# mechanical_marking.net
KiCad netlist of a schematic drawn in Altium Designer
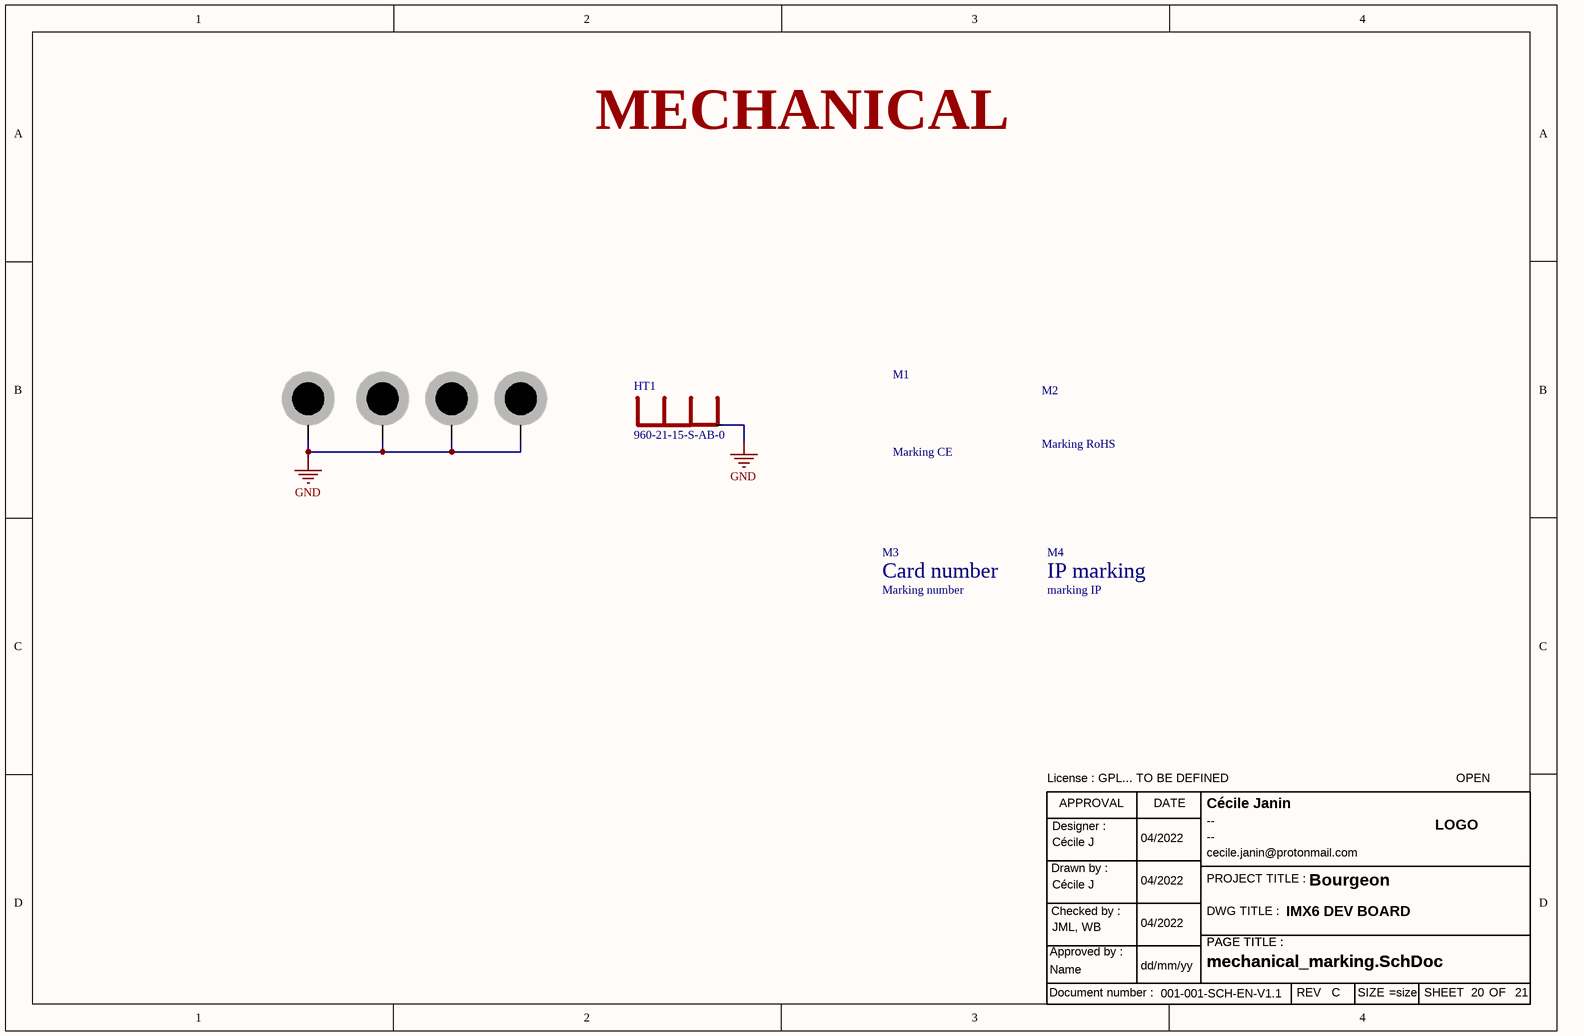
[diagram p0: mechanical_marking.SchDoc]

(export (version "E")
  (design (tool "Eeschema 10.0.6"))
  (components
    (comp (ref "HT1")
      (value "960-21-15-S-AB-0")
      (footprint "Heatsink BGA 21x21mm")
      (description "Heatsink : 960-21-15-S-AB-0\r\n6°/W @ 200LFM")
      (libsource (lib "First Board IMX6") (part "Heatsink BGA 21x21mm"))
    )
    (comp (ref "M1")
      (value "Marking CE")
      (footprint "MARKING CE")
      (description "CE marking")
      (libsource (lib "First Board IMX6") (part "Marking CE"))
    )
    (comp (ref "M2")
      (value "Marking RoHS")
      (footprint "MARKING ROHS")
      (description "RoHS marking")
      (libsource (lib "First Board IMX6") (part "Marking RoHS"))
    )
    (comp (ref "M3")
      (value "Marking number")
      (footprint "MARKING number")
      (description "Card number")
      (libsource (lib "First Board IMX6") (part "Marking number"))
    )
    (comp (ref "M4")
      (value "marking IP")
      (footprint "MARKING IP")
      (description "for IP marking")
      (libsource (lib "First Board IMX6") (part "marking IP"))
    )
    (comp (ref "MT1")
      (value "Mounting hole")
      (footprint "mountinghole")
      (description "mounting hole\r\nH : 3.2mm\r\nD : 5.2mm")
      (libsource (lib "First Board IMX6") (part "Mounting hole"))
    )
    (comp (ref "MT2")
      (value "Mounting hole")
      (footprint "mountinghole")
      (description "mounting hole\r\nH : 3.2mm\r\nD : 5.2mm")
      (libsource (lib "First Board IMX6") (part "Mounting hole"))
    )
    (comp (ref "MT3")
      (value "Mounting hole")
      (footprint "mountinghole")
      (description "mounting hole\r\nH : 3.2mm\r\nD : 5.2mm")
      (libsource (lib "First Board IMX6") (part "Mounting hole"))
    )
    (comp (ref "MT4")
      (value "Mounting hole")
      (footprint "mountinghole")
      (description "mounting hole\r\nH : 3.2mm\r\nD : 5.2mm")
      (libsource (lib "First Board IMX6") (part "Mounting hole"))
    )
    (comp (ref "TB19")
      (value "Title bloc ANSI modified")
      (libsource (lib "First Board IMX6") (part "Title bloc ANSI"))
    )
  )
  (nets
    (net (code "1") (name "GND") (class "Default")
      (node (ref "HT1") (pin "1") (pinfunction "1_1") (pintype "passive"))
      (node (ref "MT1") (pin "0") (pinfunction "0_0") (pintype "passive"))
      (node (ref "MT2") (pin "0") (pinfunction "0_0") (pintype "passive"))
      (node (ref "MT3") (pin "0") (pinfunction "0_0") (pintype "passive"))
      (node (ref "MT4") (pin "0") (pinfunction "0_0") (pintype "passive"))
    )
  )
)
